# SMS_to_Genesis.net
KiCad netlist of a schematic drawn in EAGLE
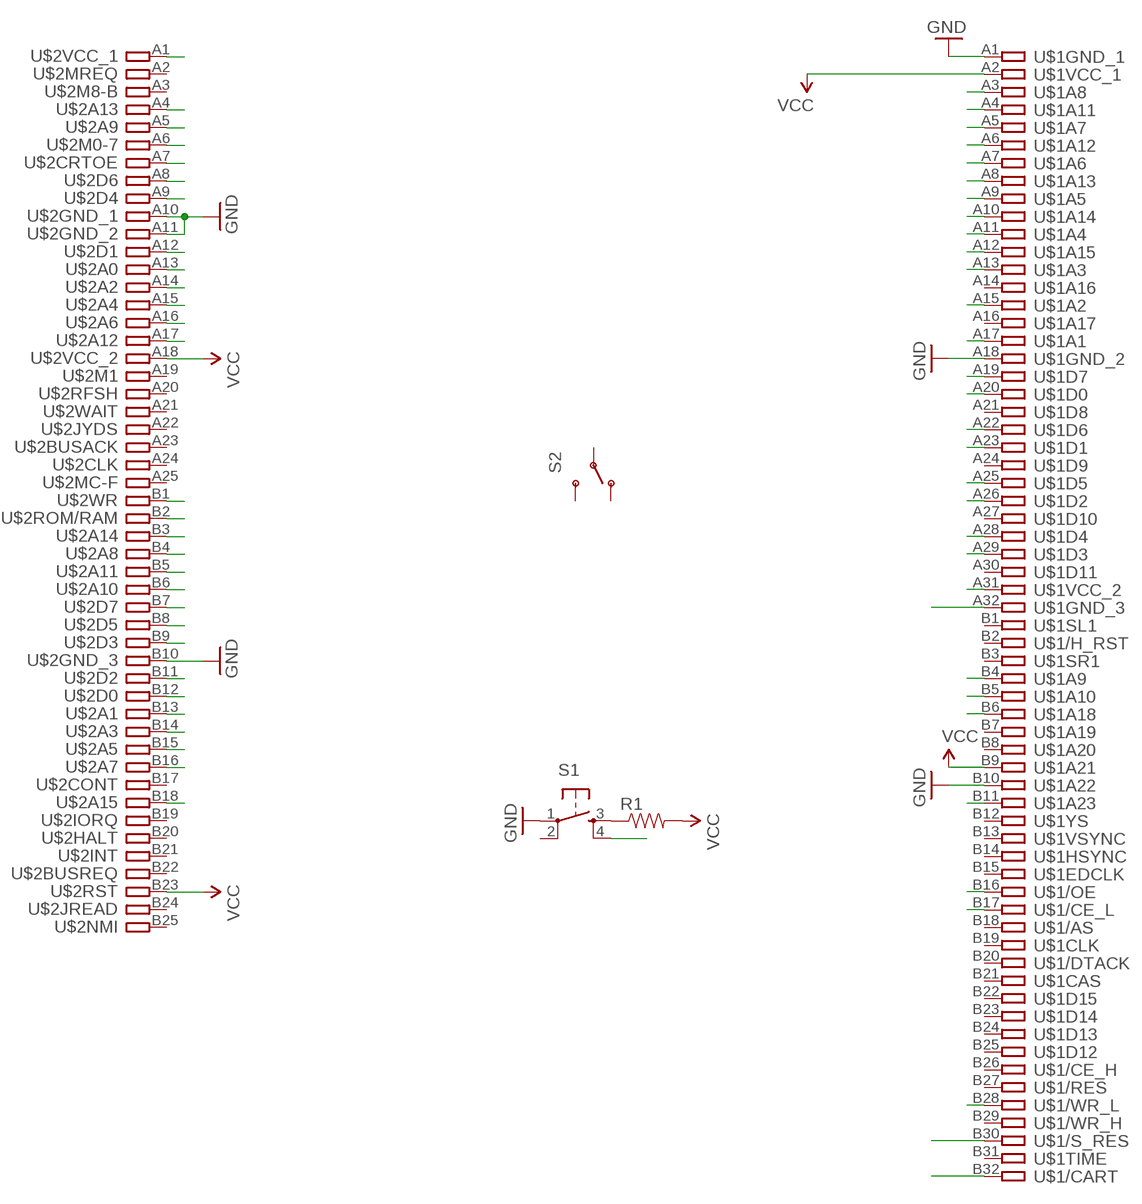
[diagram p0: schematic, sheet 1]

(export (version "E")
  (design (tool "Eeschema 10.0.6"))
  (components
    (comp (ref "R1")
      (value "RESISTOR0805-RES")
      (footprint "eagle-import:0805")
      (libsource (lib "eagle-import") (part "RESISTOR0805-RES"))
    )
    (comp (ref "S1")
      (value "TAC_SWITCHSMD")
      (footprint "eagle-import:TACTILE-SWITCH-SMD")
      (libsource (lib "eagle-import") (part "TAC_SWITCHSMD"))
    )
    (comp (ref "S2")
      (value "SWITCH-SPDTPTH")
      (footprint "eagle-import:SWITCH-SPDT")
      (libsource (lib "eagle-import") (part "SWITCH-SPDTPTH"))
    )
    (comp (ref "U$1")
      (value "GENESIS-LARGE")
      (footprint "eagle-import:GENESIS-LARGE")
      (libsource (lib "eagle-import") (part "GENESIS-LARGE"))
    )
    (comp (ref "U$2")
      (value "SMS-R")
      (footprint "eagle-import:SMS")
      (libsource (lib "eagle-import") (part "SMS-R"))
    )
  )
  (nets
    (net (code "1") (name "/A3") (class "Default")
      (node (ref "U$1") (pin "A3") (pinfunction "P_A3") (pintype "bidirectional"))
      (node (ref "U$2") (pin "B16") (pinfunction "P_B16") (pintype "passive"))
    )
    (net (code "2") (name "/A4") (class "Default")
      (node (ref "U$1") (pin "A4") (pinfunction "P_A4") (pintype "bidirectional"))
      (node (ref "U$2") (pin "B6") (pinfunction "P_B6") (pintype "passive"))
    )
    (net (code "3") (name "/A5") (class "Default")
      (node (ref "U$1") (pin "A5") (pinfunction "P_A5") (pintype "bidirectional"))
      (node (ref "U$2") (pin "A16") (pinfunction "P_A16") (pintype "passive"))
    )
    (net (code "4") (name "/A6") (class "Default")
      (node (ref "U$1") (pin "A6") (pinfunction "P_A6") (pintype "bidirectional"))
      (node (ref "U$2") (pin "B5") (pinfunction "P_B5") (pintype "passive"))
    )
    (net (code "5") (name "/A7") (class "Default")
      (node (ref "U$1") (pin "A7") (pinfunction "P_A7") (pintype "bidirectional"))
      (node (ref "U$2") (pin "B15") (pinfunction "P_B15") (pintype "passive"))
    )
    (net (code "6") (name "/A8") (class "Default")
      (node (ref "U$1") (pin "A8") (pinfunction "P_A8") (pintype "bidirectional"))
      (node (ref "U$2") (pin "A17") (pinfunction "P_A17") (pintype "passive"))
    )
    (net (code "7") (name "/A9") (class "Default")
      (node (ref "U$1") (pin "A9") (pinfunction "P_A9") (pintype "bidirectional"))
      (node (ref "U$2") (pin "A15") (pinfunction "P_A15") (pintype "passive"))
    )
    (net (code "8") (name "/A10") (class "Default")
      (node (ref "U$1") (pin "A10") (pinfunction "P_A10") (pintype "bidirectional"))
      (node (ref "U$2") (pin "A4") (pinfunction "P_A4") (pintype "passive"))
    )
    (net (code "9") (name "/A11") (class "Default")
      (node (ref "U$1") (pin "A11") (pinfunction "P_A11") (pintype "bidirectional"))
      (node (ref "U$2") (pin "B14") (pinfunction "P_B14") (pintype "passive"))
    )
    (net (code "10") (name "/A12") (class "Default")
      (node (ref "U$1") (pin "A12") (pinfunction "P_A12") (pintype "bidirectional"))
      (node (ref "U$2") (pin "B3") (pinfunction "P_B3") (pintype "passive"))
    )
    (net (code "11") (name "/A13") (class "Default")
      (node (ref "U$1") (pin "A13") (pinfunction "P_A13") (pintype "bidirectional"))
      (node (ref "U$2") (pin "A14") (pinfunction "P_A14") (pintype "passive"))
    )
    (net (code "12") (name "/A15") (class "Default")
      (node (ref "U$1") (pin "A15") (pinfunction "P_A15") (pintype "bidirectional"))
      (node (ref "U$2") (pin "B13") (pinfunction "P_B13") (pintype "passive"))
    )
    (net (code "13") (name "/A17") (class "Default")
      (node (ref "U$1") (pin "A17") (pinfunction "P_A17") (pintype "bidirectional"))
      (node (ref "U$2") (pin "A13") (pinfunction "P_A13") (pintype "passive"))
    )
    (net (code "14") (name "/A19") (class "Default")
      (node (ref "U$1") (pin "A19") (pinfunction "P_A19") (pintype "bidirectional"))
      (node (ref "U$2") (pin "B7") (pinfunction "P_B7") (pintype "passive"))
    )
    (net (code "15") (name "/A20") (class "Default")
      (node (ref "U$1") (pin "A20") (pinfunction "P_A20") (pintype "bidirectional"))
      (node (ref "U$2") (pin "B12") (pinfunction "P_B12") (pintype "passive"))
    )
    (net (code "16") (name "/A22") (class "Default")
      (node (ref "U$1") (pin "A22") (pinfunction "P_A22") (pintype "bidirectional"))
      (node (ref "U$2") (pin "A8") (pinfunction "P_A8") (pintype "passive"))
    )
    (net (code "17") (name "/A23") (class "Default")
      (node (ref "U$1") (pin "A23") (pinfunction "P_A23") (pintype "bidirectional"))
      (node (ref "U$2") (pin "A12") (pinfunction "P_A12") (pintype "passive"))
    )
    (net (code "18") (name "/A25") (class "Default")
      (node (ref "U$1") (pin "A25") (pinfunction "P_A25") (pintype "bidirectional"))
      (node (ref "U$2") (pin "B8") (pinfunction "P_B8") (pintype "passive"))
    )
    (net (code "19") (name "/A26") (class "Default")
      (node (ref "U$1") (pin "A26") (pinfunction "P_A26") (pintype "bidirectional"))
      (node (ref "U$2") (pin "B11") (pinfunction "P_B11") (pintype "passive"))
    )
    (net (code "20") (name "/A28") (class "Default")
      (node (ref "U$1") (pin "A28") (pinfunction "P_A28") (pintype "bidirectional"))
      (node (ref "U$2") (pin "A9") (pinfunction "P_A9") (pintype "passive"))
    )
    (net (code "21") (name "/A29") (class "Default")
      (node (ref "U$1") (pin "A29") (pinfunction "P_A29") (pintype "bidirectional"))
      (node (ref "U$2") (pin "B9") (pinfunction "P_B9") (pintype "passive"))
    )
    (net (code "22") (name "/A31") (class "Default")
      (node (ref "U$1") (pin "A31") (pinfunction "P_A31") (pintype "bidirectional"))
      (node (ref "U$2") (pin "A1") (pinfunction "P_A1") (pintype "passive"))
    )
    (net (code "23") (name "/B4") (class "Default")
      (node (ref "U$1") (pin "B4") (pinfunction "P_B4") (pintype "bidirectional"))
      (node (ref "U$2") (pin "B4") (pinfunction "P_B4") (pintype "passive"))
    )
    (net (code "24") (name "/B5") (class "Default")
      (node (ref "U$1") (pin "B5") (pinfunction "P_B5") (pintype "bidirectional"))
      (node (ref "U$2") (pin "A5") (pinfunction "P_A5") (pintype "passive"))
    )
    (net (code "25") (name "/B6") (class "Default")
      (node (ref "U$1") (pin "B6") (pinfunction "P_B6") (pintype "bidirectional"))
      (node (ref "U$2") (pin "A7") (pinfunction "P_A7") (pintype "passive"))
    )
    (net (code "26") (name "/B11") (class "Default")
      (node (ref "S1") (pin "4") (pinfunction "4_4") (pintype "passive"))
      (node (ref "U$1") (pin "B11") (pinfunction "P_B11") (pintype "bidirectional"))
    )
    (net (code "27") (name "/B16") (class "Default")
      (node (ref "U$1") (pin "B16") (pinfunction "P_B16") (pintype "bidirectional"))
      (node (ref "U$2") (pin "B2") (pinfunction "P_B2") (pintype "passive"))
    )
    (net (code "28") (name "/B17") (class "Default")
      (node (ref "U$1") (pin "B17") (pinfunction "P_B17") (pintype "bidirectional"))
      (node (ref "U$2") (pin "A6") (pinfunction "P_A6") (pintype "passive"))
      (node (ref "U$2") (pin "B18") (pinfunction "P_B18") (pintype "passive"))
    )
    (net (code "29") (name "/B28") (class "Default")
      (node (ref "U$1") (pin "B28") (pinfunction "P_B28") (pintype "bidirectional"))
      (node (ref "U$2") (pin "B1") (pinfunction "P_B1") (pintype "passive"))
    )
    (net (code "30") (name "/SMS") (class "Default")
      (node (ref "U$1") (pin "A32") (pinfunction "P_A32") (pintype "bidirectional"))
      (node (ref "U$1") (pin "B30") (pinfunction "P_B30") (pintype "bidirectional"))
      (node (ref "U$1") (pin "B32") (pinfunction "P_B32") (pintype "bidirectional"))
    )
    (net (code "31") (name "GND") (class "Default")
      (node (ref "S1") (pin "1") (pinfunction "1_1") (pintype "passive"))
      (node (ref "U$1") (pin "A1") (pinfunction "P_A1") (pintype "bidirectional"))
      (node (ref "U$1") (pin "A18") (pinfunction "P_A18") (pintype "bidirectional"))
      (node (ref "U$1") (pin "B10") (pinfunction "P_B10") (pintype "bidirectional"))
      (node (ref "U$2") (pin "A10") (pinfunction "P_A10") (pintype "passive"))
      (node (ref "U$2") (pin "A11") (pinfunction "P_A11") (pintype "passive"))
      (node (ref "U$2") (pin "B10") (pinfunction "P_B10") (pintype "passive"))
    )
    (net (code "32") (name "Net-(R1-Pad1)") (class "Default")
      (node (ref "R1") (pin "1") (pinfunction "1_1") (pintype "passive"))
      (node (ref "S1") (pin "3") (pinfunction "3_3") (pintype "passive"))
    )
    (net (code "33") (name "VCC") (class "Default")
      (node (ref "R1") (pin "2") (pinfunction "2_2") (pintype "passive"))
      (node (ref "U$1") (pin "A2") (pinfunction "P_A2") (pintype "bidirectional"))
      (node (ref "U$1") (pin "B9") (pinfunction "P_B9") (pintype "bidirectional"))
      (node (ref "U$2") (pin "A18") (pinfunction "P_A18") (pintype "passive"))
      (node (ref "U$2") (pin "B23") (pinfunction "P_B23") (pintype "passive"))
    )
    (net (code "34") (name "unconnected-(S1-Pad2)") (class "Default")
      (node (ref "S1") (pin "2") (pinfunction "2_2") (pintype "passive"))
    )
    (net (code "35") (name "unconnected-(S2-O-Pad1)") (class "Default")
      (node (ref "S2") (pin "1") (pinfunction "O_1") (pintype "passive"))
    )
    (net (code "36") (name "unconnected-(S2-P-Pad2)") (class "Default")
      (node (ref "S2") (pin "2") (pinfunction "P_2") (pintype "passive"))
    )
    (net (code "37") (name "unconnected-(S2-S-Pad3)") (class "Default")
      (node (ref "S2") (pin "3") (pinfunction "S_3") (pintype "passive"))
    )
    (net (code "38") (name "unconnected-(U$1A-P-PadB18)") (class "Default")
      (node (ref "U$1") (pin "B18") (pinfunction "P_B18") (pintype "bidirectional"))
    )
    (net (code "39") (name "unconnected-(U$1AI-P-PadB21)") (class "Default")
      (node (ref "U$1") (pin "B21") (pinfunction "P_B21") (pintype "bidirectional"))
    )
    (net (code "40") (name "unconnected-(U$1AJ-P-PadB19)") (class "Default")
      (node (ref "U$1") (pin "B19") (pinfunction "P_B19") (pintype "bidirectional"))
    )
    (net (code "41") (name "unconnected-(U$1AM-P-PadA27)") (class "Default")
      (node (ref "U$1") (pin "A27") (pinfunction "P_A27") (pintype "bidirectional"))
    )
    (net (code "42") (name "unconnected-(U$1AN-P-PadA30)") (class "Default")
      (node (ref "U$1") (pin "A30") (pinfunction "P_A30") (pintype "bidirectional"))
    )
    (net (code "43") (name "unconnected-(U$1AO-P-PadB25)") (class "Default")
      (node (ref "U$1") (pin "B25") (pinfunction "P_B25") (pintype "bidirectional"))
    )
    (net (code "44") (name "unconnected-(U$1AP-P-PadB24)") (class "Default")
      (node (ref "U$1") (pin "B24") (pinfunction "P_B24") (pintype "bidirectional"))
    )
    (net (code "45") (name "unconnected-(U$1AQ-P-PadB23)") (class "Default")
      (node (ref "U$1") (pin "B23") (pinfunction "P_B23") (pintype "bidirectional"))
    )
    (net (code "46") (name "unconnected-(U$1AR-P-PadB22)") (class "Default")
      (node (ref "U$1") (pin "B22") (pinfunction "P_B22") (pintype "bidirectional"))
    )
    (net (code "47") (name "unconnected-(U$1AY-P-PadA21)") (class "Default")
      (node (ref "U$1") (pin "A21") (pinfunction "P_A21") (pintype "bidirectional"))
    )
    (net (code "48") (name "unconnected-(U$1AZ-P-PadA24)") (class "Default")
      (node (ref "U$1") (pin "A24") (pinfunction "P_A24") (pintype "bidirectional"))
    )
    (net (code "49") (name "unconnected-(U$1BA-P-PadB15)") (class "Default")
      (node (ref "U$1") (pin "B15") (pinfunction "P_B15") (pintype "bidirectional"))
    )
    (net (code "50") (name "unconnected-(U$1BE-P-PadB14)") (class "Default")
      (node (ref "U$1") (pin "B14") (pinfunction "P_B14") (pintype "bidirectional"))
    )
    (net (code "51") (name "unconnected-(U$1BF-P-PadB1)") (class "Default")
      (node (ref "U$1") (pin "B1") (pinfunction "P_B1") (pintype "bidirectional"))
    )
    (net (code "52") (name "unconnected-(U$1BG-P-PadB3)") (class "Default")
      (node (ref "U$1") (pin "B3") (pinfunction "P_B3") (pintype "bidirectional"))
    )
    (net (code "53") (name "unconnected-(U$1BH-P-PadB31)") (class "Default")
      (node (ref "U$1") (pin "B31") (pinfunction "P_B31") (pintype "bidirectional"))
    )
    (net (code "54") (name "unconnected-(U$1BK-P-PadB13)") (class "Default")
      (node (ref "U$1") (pin "B13") (pinfunction "P_B13") (pintype "bidirectional"))
    )
    (net (code "55") (name "unconnected-(U$1BL-P-PadB12)") (class "Default")
      (node (ref "U$1") (pin "B12") (pinfunction "P_B12") (pintype "bidirectional"))
    )
    (net (code "56") (name "unconnected-(U$1C-P-PadB26)") (class "Default")
      (node (ref "U$1") (pin "B26") (pinfunction "P_B26") (pintype "bidirectional"))
    )
    (net (code "57") (name "unconnected-(U$1E-P-PadB20)") (class "Default")
      (node (ref "U$1") (pin "B20") (pinfunction "P_B20") (pintype "bidirectional"))
    )
    (net (code "58") (name "unconnected-(U$1F-P-PadB2)") (class "Default")
      (node (ref "U$1") (pin "B2") (pinfunction "P_B2") (pintype "bidirectional"))
    )
    (net (code "59") (name "unconnected-(U$1H-P-PadB27)") (class "Default")
      (node (ref "U$1") (pin "B27") (pinfunction "P_B27") (pintype "bidirectional"))
    )
    (net (code "60") (name "unconnected-(U$1J-P-PadB29)") (class "Default")
      (node (ref "U$1") (pin "B29") (pinfunction "P_B29") (pintype "bidirectional"))
    )
    (net (code "61") (name "unconnected-(U$1S-P-PadA14)") (class "Default")
      (node (ref "U$1") (pin "A14") (pinfunction "P_A14") (pintype "bidirectional"))
    )
    (net (code "62") (name "unconnected-(U$1T-P-PadA16)") (class "Default")
      (node (ref "U$1") (pin "A16") (pinfunction "P_A16") (pintype "bidirectional"))
    )
    (net (code "63") (name "unconnected-(U$1V-P-PadB7)") (class "Default")
      (node (ref "U$1") (pin "B7") (pinfunction "P_B7") (pintype "bidirectional"))
    )
    (net (code "64") (name "unconnected-(U$1X-P-PadB8)") (class "Default")
      (node (ref "U$1") (pin "B8") (pinfunction "P_B8") (pintype "bidirectional"))
    )
    (net (code "65") (name "unconnected-(U$2AG-P-PadB20)") (class "Default")
      (node (ref "U$2") (pin "B20") (pinfunction "P_B20") (pintype "passive"))
    )
    (net (code "66") (name "unconnected-(U$2AH-P-PadB21)") (class "Default")
      (node (ref "U$2") (pin "B21") (pinfunction "P_B21") (pintype "passive"))
    )
    (net (code "67") (name "unconnected-(U$2AI-P-PadB19)") (class "Default")
      (node (ref "U$2") (pin "B19") (pinfunction "P_B19") (pintype "passive"))
    )
    (net (code "68") (name "unconnected-(U$2AJ-P-PadB24)") (class "Default")
      (node (ref "U$2") (pin "B24") (pinfunction "P_B24") (pintype "passive"))
    )
    (net (code "69") (name "unconnected-(U$2AK-P-PadA22)") (class "Default")
      (node (ref "U$2") (pin "A22") (pinfunction "P_A22") (pintype "passive"))
    )
    (net (code "70") (name "unconnected-(U$2AM-P-PadA19)") (class "Default")
      (node (ref "U$2") (pin "A19") (pinfunction "P_A19") (pintype "passive"))
    )
    (net (code "71") (name "unconnected-(U$2AN-P-PadA3)") (class "Default")
      (node (ref "U$2") (pin "A3") (pinfunction "P_A3") (pintype "passive"))
    )
    (net (code "72") (name "unconnected-(U$2AO-P-PadA25)") (class "Default")
      (node (ref "U$2") (pin "A25") (pinfunction "P_A25") (pintype "passive"))
    )
    (net (code "73") (name "unconnected-(U$2AP-P-PadA2)") (class "Default")
      (node (ref "U$2") (pin "A2") (pinfunction "P_A2") (pintype "passive"))
    )
    (net (code "74") (name "unconnected-(U$2AQ-P-PadB25)") (class "Default")
      (node (ref "U$2") (pin "B25") (pinfunction "P_B25") (pintype "passive"))
    )
    (net (code "75") (name "unconnected-(U$2AR-P-PadA20)") (class "Default")
      (node (ref "U$2") (pin "A20") (pinfunction "P_A20") (pintype "passive"))
    )
    (net (code "76") (name "unconnected-(U$2AW-P-PadA21)") (class "Default")
      (node (ref "U$2") (pin "A21") (pinfunction "P_A21") (pintype "passive"))
    )
    (net (code "77") (name "unconnected-(U$2Q-P-PadA23)") (class "Default")
      (node (ref "U$2") (pin "A23") (pinfunction "P_A23") (pintype "passive"))
    )
    (net (code "78") (name "unconnected-(U$2R-P-PadB22)") (class "Default")
      (node (ref "U$2") (pin "B22") (pinfunction "P_B22") (pintype "passive"))
    )
    (net (code "79") (name "unconnected-(U$2S-P-PadA24)") (class "Default")
      (node (ref "U$2") (pin "A24") (pinfunction "P_A24") (pintype "passive"))
    )
    (net (code "80") (name "unconnected-(U$2T-P-PadB17)") (class "Default")
      (node (ref "U$2") (pin "B17") (pinfunction "P_B17") (pintype "passive"))
    )
  )
)
